# horta.net
KiCad netlist of a schematic drawn in EAGLE
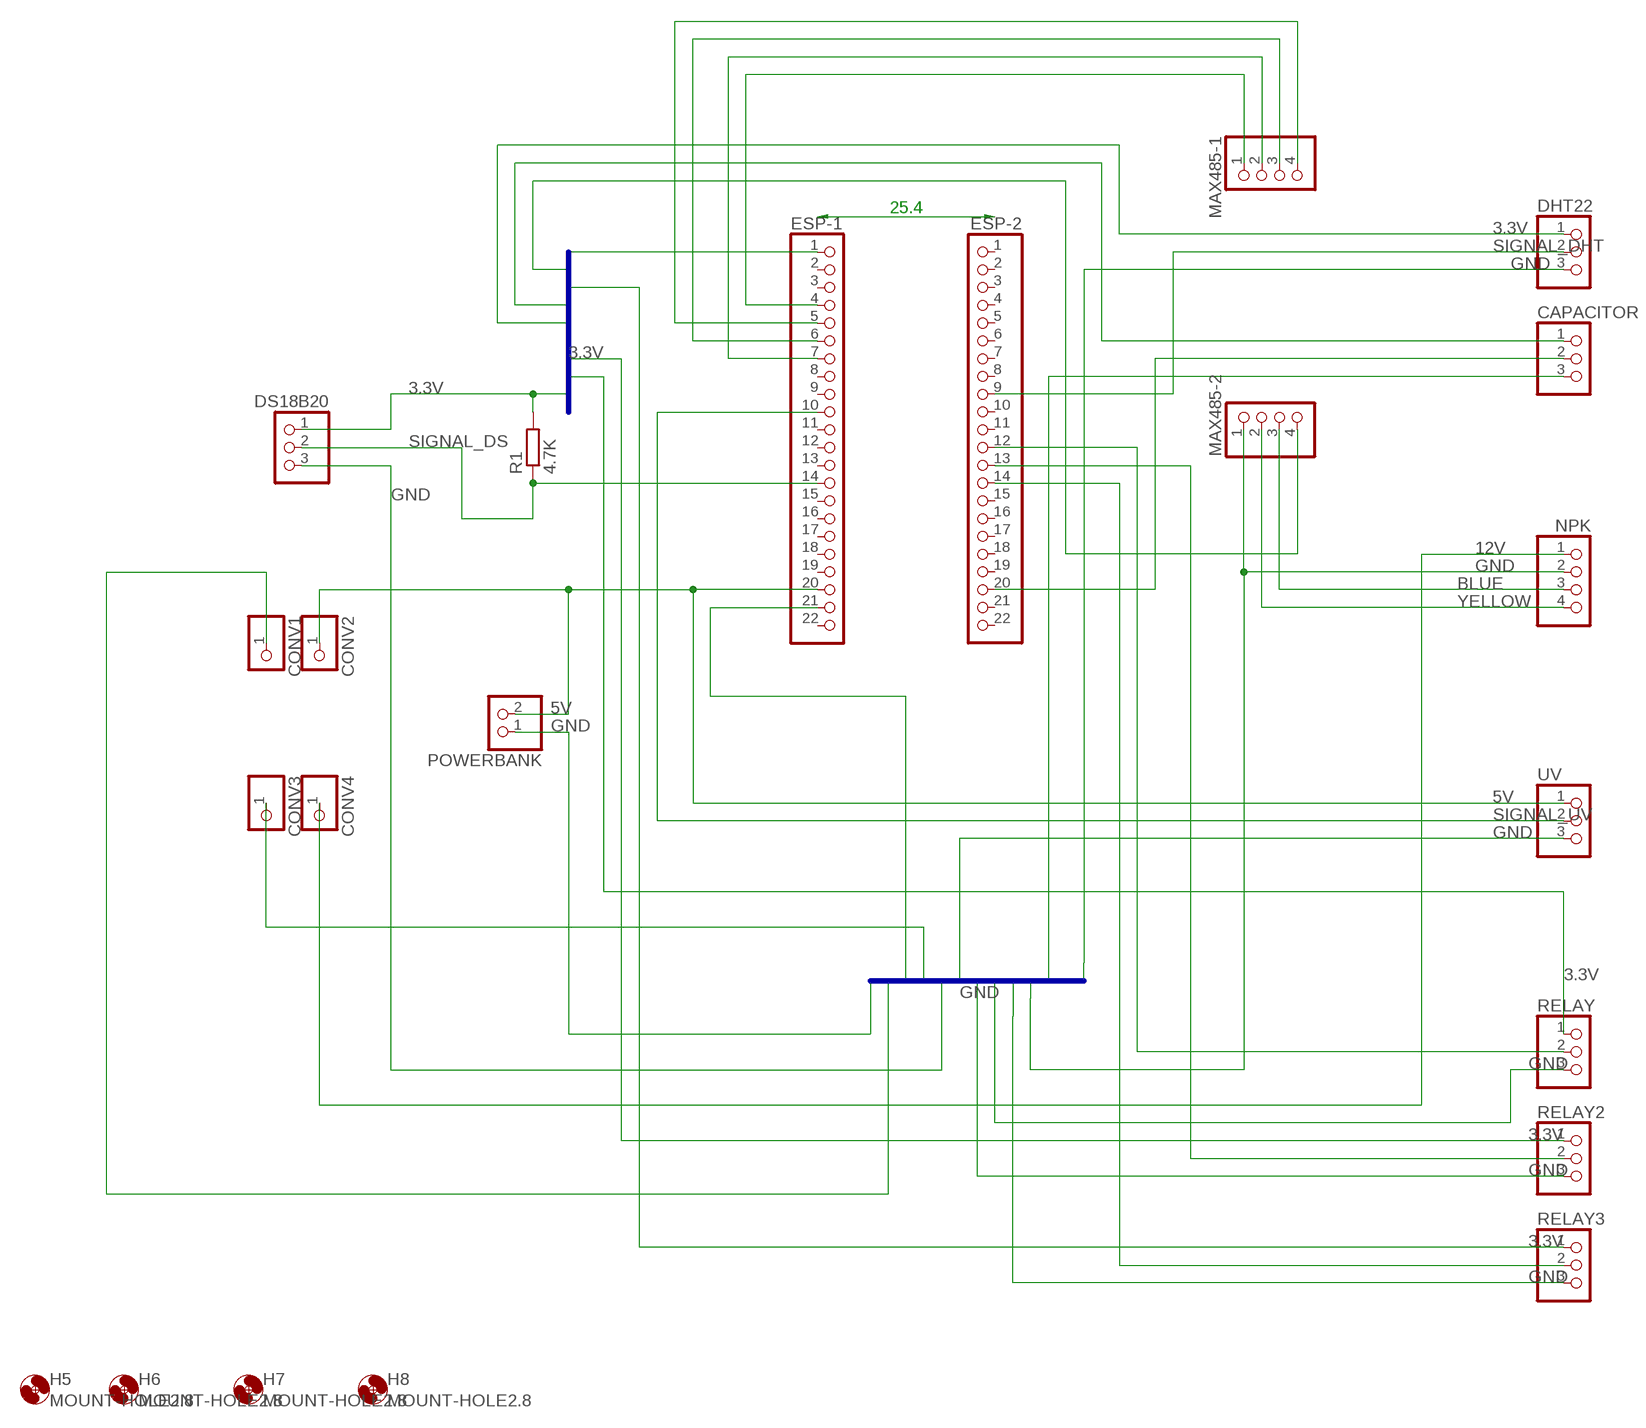
[diagram p0: schematic, sheet 1]

(export (version "E")
  (design (tool "Eeschema 10.0.6"))
  (components
    (comp (ref "CAPACITOR")
      (value "PINHD-1X3")
      (footprint "eagle-import:1X03")
      (libsource (lib "eagle-import") (part "PINHD-1X3"))
    )
    (comp (ref "CONV1")
      (value "PINHD-1X1")
      (footprint "eagle-import:1X01")
      (libsource (lib "eagle-import") (part "PINHD-1X1"))
    )
    (comp (ref "CONV2")
      (value "PINHD-1X1")
      (footprint "eagle-import:1X01")
      (libsource (lib "eagle-import") (part "PINHD-1X1"))
    )
    (comp (ref "CONV3")
      (value "PINHD-1X1")
      (footprint "eagle-import:1X01")
      (libsource (lib "eagle-import") (part "PINHD-1X1"))
    )
    (comp (ref "CONV4")
      (value "PINHD-1X1")
      (footprint "eagle-import:1X01")
      (libsource (lib "eagle-import") (part "PINHD-1X1"))
    )
    (comp (ref "DHT22")
      (value "PINHD-1X3")
      (footprint "eagle-import:1X03")
      (libsource (lib "eagle-import") (part "PINHD-1X3"))
    )
    (comp (ref "DS18B20")
      (value "PINHD-1X3")
      (footprint "eagle-import:1X03")
      (libsource (lib "eagle-import") (part "PINHD-1X3"))
    )
    (comp (ref "ESP-1")
      (value "PINHD-1X22")
      (footprint "eagle-import:1X22")
      (libsource (lib "eagle-import") (part "PINHD-1X22"))
    )
    (comp (ref "ESP-2")
      (value "PINHD-1X22")
      (footprint "eagle-import:1X22")
      (libsource (lib "eagle-import") (part "PINHD-1X22"))
    )
    (comp (ref "H5")
      (value "MOUNT-HOLE2.8")
      (footprint "eagle-import:2,8")
      (libsource (lib "eagle-import") (part "MOUNT-HOLE2.8"))
    )
    (comp (ref "H6")
      (value "MOUNT-HOLE2.8")
      (footprint "eagle-import:2,8")
      (libsource (lib "eagle-import") (part "MOUNT-HOLE2.8"))
    )
    (comp (ref "H7")
      (value "MOUNT-HOLE2.8")
      (footprint "eagle-import:2,8")
      (libsource (lib "eagle-import") (part "MOUNT-HOLE2.8"))
    )
    (comp (ref "H8")
      (value "MOUNT-HOLE2.8")
      (footprint "eagle-import:2,8")
      (libsource (lib "eagle-import") (part "MOUNT-HOLE2.8"))
    )
    (comp (ref "MAX485-1")
      (value "PINHD-1X4")
      (footprint "eagle-import:1X04")
      (libsource (lib "eagle-import") (part "PINHD-1X4"))
    )
    (comp (ref "MAX485-2")
      (value "PINHD-1X4")
      (footprint "eagle-import:1X04")
      (libsource (lib "eagle-import") (part "PINHD-1X4"))
    )
    (comp (ref "NPK")
      (value "PINHD-1X4")
      (footprint "eagle-import:1X04")
      (libsource (lib "eagle-import") (part "PINHD-1X4"))
    )
    (comp (ref "POWERBANK")
      (value "PINHD-1X2")
      (footprint "eagle-import:1X02")
      (libsource (lib "eagle-import") (part "PINHD-1X2"))
    )
    (comp (ref "R1")
      (value "4.7K")
      (footprint "eagle-import:0207_10")
      (libsource (lib "eagle-import") (part "R-EU_0207/10"))
    )
    (comp (ref "RELAY")
      (value "PINHD-1X3")
      (footprint "eagle-import:1X03")
      (libsource (lib "eagle-import") (part "PINHD-1X3"))
    )
    (comp (ref "RELAY2")
      (value "PINHD-1X3")
      (footprint "eagle-import:1X03")
      (libsource (lib "eagle-import") (part "PINHD-1X3"))
    )
    (comp (ref "RELAY3")
      (value "PINHD-1X3")
      (footprint "eagle-import:1X03")
      (libsource (lib "eagle-import") (part "PINHD-1X3"))
    )
    (comp (ref "UV")
      (value "PINHD-1X3")
      (footprint "eagle-import:1X03")
      (libsource (lib "eagle-import") (part "PINHD-1X3"))
    )
  )
  (nets
    (net (code "1") (name "/3.3V") (class "Default")
      (node (ref "CAPACITOR") (pin "1") (pinfunction "1_1") (pintype "passive"))
      (node (ref "DHT22") (pin "1") (pinfunction "1_1") (pintype "passive"))
      (node (ref "DS18B20") (pin "1") (pinfunction "1_1") (pintype "passive"))
      (node (ref "ESP-1") (pin "1") (pinfunction "1_1") (pintype "passive"))
      (node (ref "MAX485-2") (pin "4") (pinfunction "4_4") (pintype "passive"))
      (node (ref "R1") (pin "2") (pinfunction "2_2") (pintype "passive"))
      (node (ref "RELAY") (pin "1") (pinfunction "1_1") (pintype "passive"))
      (node (ref "RELAY2") (pin "1") (pinfunction "1_1") (pintype "passive"))
      (node (ref "RELAY3") (pin "1") (pinfunction "1_1") (pintype "passive"))
    )
    (net (code "2") (name "/5V") (class "Default")
      (node (ref "CONV2") (pin "1") (pinfunction "1_1") (pintype "passive"))
      (node (ref "ESP-1") (pin "20") (pinfunction "20_20") (pintype "passive"))
      (node (ref "POWERBANK") (pin "2") (pinfunction "2_2") (pintype "passive"))
      (node (ref "UV") (pin "1") (pinfunction "1_1") (pintype "passive"))
    )
    (net (code "3") (name "/12V") (class "Default")
      (node (ref "CONV4") (pin "1") (pinfunction "1_1") (pintype "passive"))
      (node (ref "NPK") (pin "1") (pinfunction "1_1") (pintype "passive"))
    )
    (net (code "4") (name "/BLUE") (class "Default")
      (node (ref "MAX485-2") (pin "3") (pinfunction "3_3") (pintype "passive"))
      (node (ref "NPK") (pin "3") (pinfunction "3_3") (pintype "passive"))
    )
    (net (code "5") (name "/GND") (class "Default")
      (node (ref "CAPACITOR") (pin "3") (pinfunction "3_3") (pintype "passive"))
      (node (ref "CONV1") (pin "1") (pinfunction "1_1") (pintype "passive"))
      (node (ref "CONV3") (pin "1") (pinfunction "1_1") (pintype "passive"))
      (node (ref "DHT22") (pin "3") (pinfunction "3_3") (pintype "passive"))
      (node (ref "DS18B20") (pin "3") (pinfunction "3_3") (pintype "passive"))
      (node (ref "ESP-1") (pin "21") (pinfunction "21_21") (pintype "passive"))
      (node (ref "MAX485-2") (pin "1") (pinfunction "1_1") (pintype "passive"))
      (node (ref "NPK") (pin "2") (pinfunction "2_2") (pintype "passive"))
      (node (ref "POWERBANK") (pin "1") (pinfunction "1_1") (pintype "passive"))
      (node (ref "RELAY") (pin "3") (pinfunction "3_3") (pintype "passive"))
      (node (ref "RELAY2") (pin "3") (pinfunction "3_3") (pintype "passive"))
      (node (ref "RELAY3") (pin "3") (pinfunction "3_3") (pintype "passive"))
      (node (ref "UV") (pin "3") (pinfunction "3_3") (pintype "passive"))
    )
    (net (code "6") (name "/SIGNAL_DHT") (class "Default")
      (node (ref "DHT22") (pin "2") (pinfunction "2_2") (pintype "passive"))
      (node (ref "ESP-2") (pin "9") (pinfunction "9_9") (pintype "passive"))
    )
    (net (code "7") (name "/SIGNAL_DS") (class "Default")
      (node (ref "DS18B20") (pin "2") (pinfunction "2_2") (pintype "passive"))
      (node (ref "ESP-1") (pin "14") (pinfunction "14_14") (pintype "passive"))
      (node (ref "R1") (pin "1") (pinfunction "1_1") (pintype "passive"))
    )
    (net (code "8") (name "/SIGNAL_UV") (class "Default")
      (node (ref "ESP-1") (pin "10") (pinfunction "10_10") (pintype "passive"))
      (node (ref "UV") (pin "2") (pinfunction "2_2") (pintype "passive"))
    )
    (net (code "9") (name "/YELLOW") (class "Default")
      (node (ref "MAX485-2") (pin "2") (pinfunction "2_2") (pintype "passive"))
      (node (ref "NPK") (pin "4") (pinfunction "4_4") (pintype "passive"))
    )
    (net (code "12") (name "Net-(CAPACITOR-Pad2)") (class "Default")
      (node (ref "CAPACITOR") (pin "2") (pinfunction "2_2") (pintype "passive"))
      (node (ref "ESP-2") (pin "20") (pinfunction "20_20") (pintype "passive"))
    )
    (net (code "13") (name "Net-(ESP-1-Pad4)") (class "Default")
      (node (ref "ESP-1") (pin "4") (pinfunction "4_4") (pintype "passive"))
      (node (ref "MAX485-1") (pin "1") (pinfunction "1_1") (pintype "passive"))
    )
    (net (code "14") (name "Net-(ESP-1-Pad5)") (class "Default")
      (node (ref "ESP-1") (pin "5") (pinfunction "5_5") (pintype "passive"))
      (node (ref "MAX485-1") (pin "4") (pinfunction "4_4") (pintype "passive"))
    )
    (net (code "15") (name "Net-(ESP-1-Pad6)") (class "Default")
      (node (ref "ESP-1") (pin "6") (pinfunction "6_6") (pintype "passive"))
      (node (ref "MAX485-1") (pin "3") (pinfunction "3_3") (pintype "passive"))
    )
    (net (code "16") (name "Net-(ESP-1-Pad7)") (class "Default")
      (node (ref "ESP-1") (pin "7") (pinfunction "7_7") (pintype "passive"))
      (node (ref "MAX485-1") (pin "2") (pinfunction "2_2") (pintype "passive"))
    )
    (net (code "17") (name "Net-(ESP-2-Pad12)") (class "Default")
      (node (ref "ESP-2") (pin "12") (pinfunction "12_12") (pintype "passive"))
      (node (ref "RELAY") (pin "2") (pinfunction "2_2") (pintype "passive"))
    )
    (net (code "18") (name "Net-(ESP-2-Pad13)") (class "Default")
      (node (ref "ESP-2") (pin "13") (pinfunction "13_13") (pintype "passive"))
      (node (ref "RELAY2") (pin "2") (pinfunction "2_2") (pintype "passive"))
    )
    (net (code "19") (name "Net-(ESP-2-Pad14)") (class "Default")
      (node (ref "ESP-2") (pin "14") (pinfunction "14_14") (pintype "passive"))
      (node (ref "RELAY3") (pin "2") (pinfunction "2_2") (pintype "passive"))
    )
    (net (code "20") (name "unconnected-(ESP-1-Pad2)") (class "Default")
      (node (ref "ESP-1") (pin "2") (pinfunction "2_2") (pintype "passive"))
    )
    (net (code "21") (name "unconnected-(ESP-1-Pad3)") (class "Default")
      (node (ref "ESP-1") (pin "3") (pinfunction "3_3") (pintype "passive"))
    )
    (net (code "22") (name "unconnected-(ESP-1-Pad8)") (class "Default")
      (node (ref "ESP-1") (pin "8") (pinfunction "8_8") (pintype "passive"))
    )
    (net (code "23") (name "unconnected-(ESP-1-Pad9)") (class "Default")
      (node (ref "ESP-1") (pin "9") (pinfunction "9_9") (pintype "passive"))
    )
    (net (code "24") (name "unconnected-(ESP-1-Pad11)") (class "Default")
      (node (ref "ESP-1") (pin "11") (pinfunction "11_11") (pintype "passive"))
    )
    (net (code "25") (name "unconnected-(ESP-1-Pad12)") (class "Default")
      (node (ref "ESP-1") (pin "12") (pinfunction "12_12") (pintype "passive"))
    )
    (net (code "26") (name "unconnected-(ESP-1-Pad13)") (class "Default")
      (node (ref "ESP-1") (pin "13") (pinfunction "13_13") (pintype "passive"))
    )
    (net (code "27") (name "unconnected-(ESP-1-Pad15)") (class "Default")
      (node (ref "ESP-1") (pin "15") (pinfunction "15_15") (pintype "passive"))
    )
    (net (code "28") (name "unconnected-(ESP-1-Pad16)") (class "Default")
      (node (ref "ESP-1") (pin "16") (pinfunction "16_16") (pintype "passive"))
    )
    (net (code "29") (name "unconnected-(ESP-1-Pad17)") (class "Default")
      (node (ref "ESP-1") (pin "17") (pinfunction "17_17") (pintype "passive"))
    )
    (net (code "30") (name "unconnected-(ESP-1-Pad18)") (class "Default")
      (node (ref "ESP-1") (pin "18") (pinfunction "18_18") (pintype "passive"))
    )
    (net (code "31") (name "unconnected-(ESP-1-Pad19)") (class "Default")
      (node (ref "ESP-1") (pin "19") (pinfunction "19_19") (pintype "passive"))
    )
    (net (code "32") (name "unconnected-(ESP-1-Pad22)") (class "Default")
      (node (ref "ESP-1") (pin "22") (pinfunction "22_22") (pintype "passive"))
    )
    (net (code "33") (name "unconnected-(ESP-2-Pad1)") (class "Default")
      (node (ref "ESP-2") (pin "1") (pinfunction "1_1") (pintype "passive"))
    )
    (net (code "34") (name "unconnected-(ESP-2-Pad2)") (class "Default")
      (node (ref "ESP-2") (pin "2") (pinfunction "2_2") (pintype "passive"))
    )
    (net (code "35") (name "unconnected-(ESP-2-Pad3)") (class "Default")
      (node (ref "ESP-2") (pin "3") (pinfunction "3_3") (pintype "passive"))
    )
    (net (code "36") (name "unconnected-(ESP-2-Pad4)") (class "Default")
      (node (ref "ESP-2") (pin "4") (pinfunction "4_4") (pintype "passive"))
    )
    (net (code "37") (name "unconnected-(ESP-2-Pad5)") (class "Default")
      (node (ref "ESP-2") (pin "5") (pinfunction "5_5") (pintype "passive"))
    )
    (net (code "38") (name "unconnected-(ESP-2-Pad6)") (class "Default")
      (node (ref "ESP-2") (pin "6") (pinfunction "6_6") (pintype "passive"))
    )
    (net (code "39") (name "unconnected-(ESP-2-Pad7)") (class "Default")
      (node (ref "ESP-2") (pin "7") (pinfunction "7_7") (pintype "passive"))
    )
    (net (code "40") (name "unconnected-(ESP-2-Pad8)") (class "Default")
      (node (ref "ESP-2") (pin "8") (pinfunction "8_8") (pintype "passive"))
    )
    (net (code "41") (name "unconnected-(ESP-2-Pad10)") (class "Default")
      (node (ref "ESP-2") (pin "10") (pinfunction "10_10") (pintype "passive"))
    )
    (net (code "42") (name "unconnected-(ESP-2-Pad11)") (class "Default")
      (node (ref "ESP-2") (pin "11") (pinfunction "11_11") (pintype "passive"))
    )
    (net (code "43") (name "unconnected-(ESP-2-Pad15)") (class "Default")
      (node (ref "ESP-2") (pin "15") (pinfunction "15_15") (pintype "passive"))
    )
    (net (code "44") (name "unconnected-(ESP-2-Pad16)") (class "Default")
      (node (ref "ESP-2") (pin "16") (pinfunction "16_16") (pintype "passive"))
    )
    (net (code "45") (name "unconnected-(ESP-2-Pad17)") (class "Default")
      (node (ref "ESP-2") (pin "17") (pinfunction "17_17") (pintype "passive"))
    )
    (net (code "46") (name "unconnected-(ESP-2-Pad18)") (class "Default")
      (node (ref "ESP-2") (pin "18") (pinfunction "18_18") (pintype "passive"))
    )
    (net (code "47") (name "unconnected-(ESP-2-Pad19)") (class "Default")
      (node (ref "ESP-2") (pin "19") (pinfunction "19_19") (pintype "passive"))
    )
    (net (code "48") (name "unconnected-(ESP-2-Pad21)") (class "Default")
      (node (ref "ESP-2") (pin "21") (pinfunction "21_21") (pintype "passive"))
    )
    (net (code "49") (name "unconnected-(ESP-2-Pad22)") (class "Default")
      (node (ref "ESP-2") (pin "22") (pinfunction "22_22") (pintype "passive"))
    )
  )
)
